# magnetoV2_0.net
KiCad netlist of a schematic drawn in EAGLE
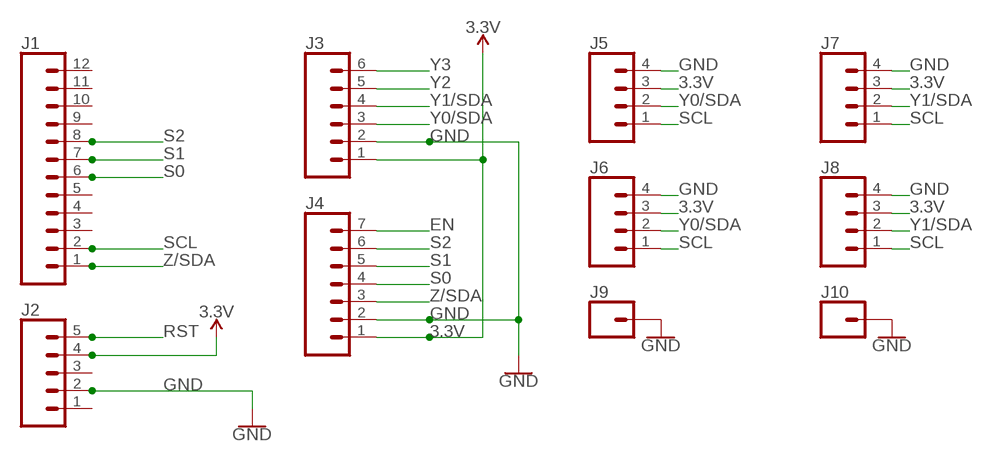
[diagram p0: schematic, sheet 1]

(export (version "E")
  (design (tool "Eeschema 10.0.6"))
  (components
    (comp (ref "J1")
      (value "CONN_12")
      (footprint "eagle-import:1X12")
      (libsource (lib "eagle-import") (part "CONN_12"))
    )
    (comp (ref "J2")
      (value "CONN_05")
      (footprint "eagle-import:1X05")
      (libsource (lib "eagle-import") (part "CONN_05"))
    )
    (comp (ref "J3")
      (value "CONN_06SILK_FEMALE_PTH")
      (footprint "eagle-import:1X06")
      (libsource (lib "eagle-import") (part "CONN_06SILK_FEMALE_PTH"))
    )
    (comp (ref "J4")
      (value "CONN_07")
      (footprint "eagle-import:1X07")
      (libsource (lib "eagle-import") (part "CONN_07"))
    )
    (comp (ref "J5")
      (value "CONN_04")
      (footprint "eagle-import:1X04")
      (libsource (lib "eagle-import") (part "CONN_04"))
    )
    (comp (ref "J6")
      (value "CONN_04")
      (footprint "eagle-import:1X04")
      (libsource (lib "eagle-import") (part "CONN_04"))
    )
    (comp (ref "J7")
      (value "CONN_04")
      (footprint "eagle-import:1X04")
      (libsource (lib "eagle-import") (part "CONN_04"))
    )
    (comp (ref "J8")
      (value "CONN_04")
      (footprint "eagle-import:1X04")
      (libsource (lib "eagle-import") (part "CONN_04"))
    )
    (comp (ref "J9")
      (value "CONN_01")
      (footprint "eagle-import:1X01")
      (libsource (lib "eagle-import") (part "CONN_01"))
    )
    (comp (ref "J10")
      (value "CONN_01")
      (footprint "eagle-import:1X01")
      (libsource (lib "eagle-import") (part "CONN_01"))
    )
  )
  (nets
    (net (code "1") (name "/EN") (class "Default")
      (node (ref "J4") (pin "7") (pinfunction "7_7") (pintype "passive"))
    )
    (net (code "2") (name "/RST") (class "Default")
      (node (ref "J2") (pin "5") (pinfunction "5_5") (pintype "passive"))
    )
    (net (code "3") (name "/S0") (class "Default")
      (node (ref "J1") (pin "6") (pinfunction "6_6") (pintype "passive"))
      (node (ref "J4") (pin "4") (pinfunction "4_4") (pintype "passive"))
    )
    (net (code "4") (name "/S1") (class "Default")
      (node (ref "J1") (pin "7") (pinfunction "7_7") (pintype "passive"))
      (node (ref "J4") (pin "5") (pinfunction "5_5") (pintype "passive"))
    )
    (net (code "5") (name "/S2") (class "Default")
      (node (ref "J1") (pin "8") (pinfunction "8_8") (pintype "passive"))
      (node (ref "J4") (pin "6") (pinfunction "6_6") (pintype "passive"))
    )
    (net (code "6") (name "/SCL") (class "Default")
      (node (ref "J1") (pin "2") (pinfunction "2_2") (pintype "passive"))
      (node (ref "J5") (pin "1") (pinfunction "1_1") (pintype "passive"))
      (node (ref "J6") (pin "1") (pinfunction "1_1") (pintype "passive"))
      (node (ref "J7") (pin "1") (pinfunction "1_1") (pintype "passive"))
      (node (ref "J8") (pin "1") (pinfunction "1_1") (pintype "passive"))
    )
    (net (code "7") (name "/Y0{slash}SDA") (class "Default")
      (node (ref "J3") (pin "3") (pinfunction "3_3") (pintype "passive"))
      (node (ref "J5") (pin "2") (pinfunction "2_2") (pintype "passive"))
      (node (ref "J6") (pin "2") (pinfunction "2_2") (pintype "passive"))
    )
    (net (code "8") (name "/Y1{slash}SDA") (class "Default")
      (node (ref "J3") (pin "4") (pinfunction "4_4") (pintype "passive"))
      (node (ref "J7") (pin "2") (pinfunction "2_2") (pintype "passive"))
      (node (ref "J8") (pin "2") (pinfunction "2_2") (pintype "passive"))
    )
    (net (code "9") (name "/Y2") (class "Default")
      (node (ref "J3") (pin "5") (pinfunction "5_5") (pintype "passive"))
    )
    (net (code "10") (name "/Y3") (class "Default")
      (node (ref "J3") (pin "6") (pinfunction "6_6") (pintype "passive"))
    )
    (net (code "11") (name "/Z{slash}SDA") (class "Default")
      (node (ref "J1") (pin "1") (pinfunction "1_1") (pintype "passive"))
      (node (ref "J4") (pin "3") (pinfunction "3_3") (pintype "passive"))
    )
    (net (code "12") (name "3.3V") (class "Default")
      (node (ref "J2") (pin "4") (pinfunction "4_4") (pintype "passive"))
      (node (ref "J3") (pin "1") (pinfunction "1_1") (pintype "passive"))
      (node (ref "J4") (pin "1") (pinfunction "1_1") (pintype "passive"))
      (node (ref "J5") (pin "3") (pinfunction "3_3") (pintype "passive"))
      (node (ref "J6") (pin "3") (pinfunction "3_3") (pintype "passive"))
      (node (ref "J7") (pin "3") (pinfunction "3_3") (pintype "passive"))
      (node (ref "J8") (pin "3") (pinfunction "3_3") (pintype "passive"))
    )
    (net (code "13") (name "GND") (class "Default")
      (node (ref "J10") (pin "1") (pinfunction "1_1") (pintype "passive"))
      (node (ref "J2") (pin "2") (pinfunction "2_2") (pintype "passive"))
      (node (ref "J3") (pin "2") (pinfunction "2_2") (pintype "passive"))
      (node (ref "J4") (pin "2") (pinfunction "2_2") (pintype "passive"))
      (node (ref "J5") (pin "4") (pinfunction "4_4") (pintype "passive"))
      (node (ref "J6") (pin "4") (pinfunction "4_4") (pintype "passive"))
      (node (ref "J7") (pin "4") (pinfunction "4_4") (pintype "passive"))
      (node (ref "J8") (pin "4") (pinfunction "4_4") (pintype "passive"))
      (node (ref "J9") (pin "1") (pinfunction "1_1") (pintype "passive"))
    )
    (net (code "14") (name "unconnected-(J1-Pad3)") (class "Default")
      (node (ref "J1") (pin "3") (pinfunction "3_3") (pintype "passive"))
    )
    (net (code "15") (name "unconnected-(J1-Pad4)") (class "Default")
      (node (ref "J1") (pin "4") (pinfunction "4_4") (pintype "passive"))
    )
    (net (code "16") (name "unconnected-(J1-Pad5)") (class "Default")
      (node (ref "J1") (pin "5") (pinfunction "5_5") (pintype "passive"))
    )
    (net (code "17") (name "unconnected-(J1-Pad9)") (class "Default")
      (node (ref "J1") (pin "9") (pinfunction "9_9") (pintype "passive"))
    )
    (net (code "18") (name "unconnected-(J1-Pad10)") (class "Default")
      (node (ref "J1") (pin "10") (pinfunction "10_10") (pintype "passive"))
    )
    (net (code "19") (name "unconnected-(J1-Pad11)") (class "Default")
      (node (ref "J1") (pin "11") (pinfunction "11_11") (pintype "passive"))
    )
    (net (code "20") (name "unconnected-(J1-Pad12)") (class "Default")
      (node (ref "J1") (pin "12") (pinfunction "12_12") (pintype "passive"))
    )
    (net (code "21") (name "unconnected-(J2-Pad1)") (class "Default")
      (node (ref "J2") (pin "1") (pinfunction "1_1") (pintype "passive"))
    )
    (net (code "22") (name "unconnected-(J2-Pad3)") (class "Default")
      (node (ref "J2") (pin "3") (pinfunction "3_3") (pintype "passive"))
    )
  )
)
